# RGB_LED_driver.net
KiCad netlist of a schematic drawn in EAGLE
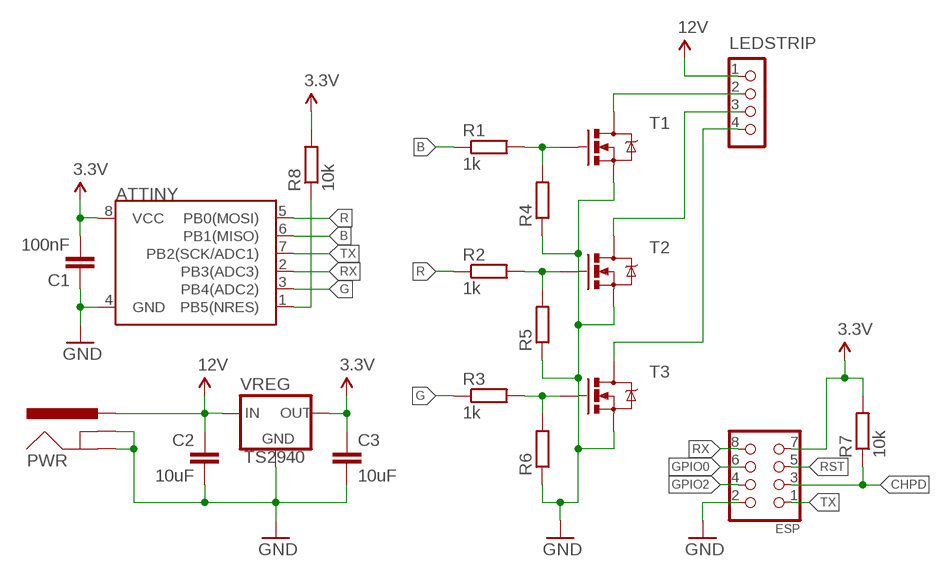
[diagram p0: schematic, sheet 1]

(export (version "E")
  (design (tool "Eeschema 10.0.6"))
  (components
    (comp (ref "ATTINY")
      (value "ATTINY45TINY85-20-SMT")
      (footprint "eagle-import:SO08-EIAJ")
      (libsource (lib "eagle-import") (part "ATTINY45TINY85-20-SMT"))
    )
    (comp (ref "C1")
      (value "100nF")
      (footprint "eagle-import:0805")
      (libsource (lib "eagle-import") (part "CAP0805"))
    )
    (comp (ref "C2")
      (value "10uF")
      (footprint "eagle-import:0805")
      (libsource (lib "eagle-import") (part "CAP0805"))
    )
    (comp (ref "C3")
      (value "10uF")
      (footprint "eagle-import:0805")
      (libsource (lib "eagle-import") (part "CAP0805"))
    )
    (comp (ref "ESP")
      (value "CON_HEADER_2X04-PTH")
      (footprint "eagle-import:M2X4")
      (libsource (lib "eagle-import") (part "CON_HEADER_2X04-PTH"))
    )
    (comp (ref "LEDSTRIP")
      (value "12vBRG")
      (footprint "eagle-import:M1X4")
      (libsource (lib "eagle-import") (part "CON_HEADER_1X04"))
    )
    (comp (ref "PWR")
      (value "POWER_JACKPTH")
      (footprint "eagle-import:POWER_JACK_PTH")
      (libsource (lib "eagle-import") (part "POWER_JACKPTH"))
    )
    (comp (ref "R1")
      (value "1k")
      (footprint "eagle-import:R603")
      (libsource (lib "eagle-import") (part "RESISTOR-0603"))
    )
    (comp (ref "R2")
      (value "1k")
      (footprint "eagle-import:R603")
      (libsource (lib "eagle-import") (part "RESISTOR-0603"))
    )
    (comp (ref "R3")
      (value "1k")
      (footprint "eagle-import:R603")
      (libsource (lib "eagle-import") (part "RESISTOR-0603"))
    )
    (comp (ref "R4")
      (value "RESISTOR-0603")
      (footprint "eagle-import:R603")
      (libsource (lib "eagle-import") (part "RESISTOR-0603"))
    )
    (comp (ref "R5")
      (value "RESISTOR-0603")
      (footprint "eagle-import:R603")
      (libsource (lib "eagle-import") (part "RESISTOR-0603"))
    )
    (comp (ref "R6")
      (value "RESISTOR-0603")
      (footprint "eagle-import:R603")
      (libsource (lib "eagle-import") (part "RESISTOR-0603"))
    )
    (comp (ref "R7")
      (value "10k")
      (footprint "eagle-import:R603")
      (libsource (lib "eagle-import") (part "RESISTOR-0603"))
    )
    (comp (ref "R8")
      (value "10k")
      (footprint "eagle-import:R603")
      (libsource (lib "eagle-import") (part "RESISTOR-0603"))
    )
    (comp (ref "T1")
      (value "MOSFET-NCHANNELFDD8780")
      (footprint "eagle-import:DPAK")
      (libsource (lib "eagle-import") (part "MOSFET-NCHANNELFDD8780"))
    )
    (comp (ref "T2")
      (value "MOSFET-NCHANNELFDD8780")
      (footprint "eagle-import:DPAK")
      (libsource (lib "eagle-import") (part "MOSFET-NCHANNELFDD8780"))
    )
    (comp (ref "T3")
      (value "MOSFET-NCHANNELFDD8780")
      (footprint "eagle-import:DPAK")
      (libsource (lib "eagle-import") (part "MOSFET-NCHANNELFDD8780"))
    )
    (comp (ref "VREG")
      (value "TS2940")
      (footprint "eagle-import:SOT223")
      (libsource (lib "eagle-import") (part "V_REG_MIC2920"))
    )
  )
  (nets
    (net (code "1") (name "3.3V") (class "Default")
      (node (ref "ATTINY") (pin "8") (pinfunction "VCC_8") (pintype "bidirectional"))
      (node (ref "C1") (pin "2") (pinfunction "2_2") (pintype "passive"))
      (node (ref "C3") (pin "1") (pinfunction "1_1") (pintype "passive"))
      (node (ref "ESP") (pin "7") (pinfunction "P$7_7") (pintype "passive"))
      (node (ref "R7") (pin "2") (pinfunction "2_2") (pintype "passive"))
      (node (ref "R8") (pin "2") (pinfunction "2_2") (pintype "passive"))
      (node (ref "VREG") (pin "3") (pinfunction "OUT_3") (pintype "output"))
    )
    (net (code "2") (name "12V") (class "Default")
      (node (ref "C2") (pin "1") (pinfunction "1_1") (pintype "passive"))
      (node (ref "LEDSTRIP") (pin "1") (pinfunction "1_1") (pintype "bidirectional"))
      (node (ref "PWR") (pin "PWR") (pinfunction "PWR_PWR") (pintype "bidirectional"))
      (node (ref "VREG") (pin "1") (pinfunction "IN_1") (pintype "input"))
    )
    (net (code "3") (name "B") (class "Default")
      (node (ref "ATTINY") (pin "6") (pinfunction "PB1(MISO)_6") (pintype "bidirectional"))
      (node (ref "R1") (pin "1") (pinfunction "1_1") (pintype "passive"))
    )
    (net (code "4") (name "CHPD") (class "Default")
      (node (ref "ESP") (pin "3") (pinfunction "P$3_3") (pintype "passive"))
      (node (ref "R7") (pin "1") (pinfunction "1_1") (pintype "passive"))
    )
    (net (code "5") (name "G") (class "Default")
      (node (ref "ATTINY") (pin "3") (pinfunction "PB4(ADC2)_3") (pintype "bidirectional"))
      (node (ref "R3") (pin "1") (pinfunction "1_1") (pintype "passive"))
    )
    (net (code "6") (name "GND") (class "Default")
      (node (ref "ATTINY") (pin "4") (pinfunction "GND_4") (pintype "bidirectional"))
      (node (ref "C1") (pin "1") (pinfunction "1_1") (pintype "passive"))
      (node (ref "C2") (pin "2") (pinfunction "2_2") (pintype "passive"))
      (node (ref "C3") (pin "2") (pinfunction "2_2") (pintype "passive"))
      (node (ref "ESP") (pin "2") (pinfunction "P$2_2") (pintype "passive"))
      (node (ref "PWR") (pin "GND") (pinfunction "GND_GND") (pintype "bidirectional"))
      (node (ref "PWR") (pin "GNDBREAK") (pinfunction "GNDBREAK_GNDBREAK") (pintype "bidirectional"))
      (node (ref "R4") (pin "1") (pinfunction "1_1") (pintype "passive"))
      (node (ref "R5") (pin "1") (pinfunction "1_1") (pintype "passive"))
      (node (ref "R6") (pin "1") (pinfunction "1_1") (pintype "passive"))
      (node (ref "T1") (pin "3") (pinfunction "S_3") (pintype "passive"))
      (node (ref "T2") (pin "3") (pinfunction "S_3") (pintype "passive"))
      (node (ref "T3") (pin "3") (pinfunction "S_3") (pintype "passive"))
      (node (ref "VREG") (pin "2") (pinfunction "GND_2") (pintype "input"))
      (node (ref "VREG") (pin "4") (pinfunction "GND_4") (pintype "input"))
    )
    (net (code "7") (name "GPIO0") (class "Default")
      (node (ref "ESP") (pin "6") (pinfunction "P$6_6") (pintype "passive"))
    )
    (net (code "8") (name "GPIO2") (class "Default")
      (node (ref "ESP") (pin "4") (pinfunction "P$4_4") (pintype "passive"))
    )
    (net (code "9") (name "Net-(ATTINY-PB5(NRES))") (class "Default")
      (node (ref "ATTINY") (pin "1") (pinfunction "PB5(NRES)_1") (pintype "bidirectional"))
      (node (ref "R8") (pin "1") (pinfunction "1_1") (pintype "passive"))
    )
    (net (code "10") (name "Net-(T1-D)") (class "Default")
      (node (ref "LEDSTRIP") (pin "2") (pinfunction "2_2") (pintype "bidirectional"))
      (node (ref "T1") (pin "4") (pinfunction "D_4") (pintype "passive"))
    )
    (net (code "11") (name "Net-(T1-G)") (class "Default")
      (node (ref "R1") (pin "2") (pinfunction "2_2") (pintype "passive"))
      (node (ref "R4") (pin "2") (pinfunction "2_2") (pintype "passive"))
      (node (ref "T1") (pin "1") (pinfunction "G_1") (pintype "passive"))
    )
    (net (code "12") (name "Net-(T2-D)") (class "Default")
      (node (ref "LEDSTRIP") (pin "3") (pinfunction "3_3") (pintype "bidirectional"))
      (node (ref "T2") (pin "4") (pinfunction "D_4") (pintype "passive"))
    )
    (net (code "13") (name "Net-(T2-G)") (class "Default")
      (node (ref "R2") (pin "2") (pinfunction "2_2") (pintype "passive"))
      (node (ref "R5") (pin "2") (pinfunction "2_2") (pintype "passive"))
      (node (ref "T2") (pin "1") (pinfunction "G_1") (pintype "passive"))
    )
    (net (code "14") (name "Net-(T3-D)") (class "Default")
      (node (ref "LEDSTRIP") (pin "4") (pinfunction "4_4") (pintype "bidirectional"))
      (node (ref "T3") (pin "4") (pinfunction "D_4") (pintype "passive"))
    )
    (net (code "15") (name "Net-(T3-G)") (class "Default")
      (node (ref "R3") (pin "2") (pinfunction "2_2") (pintype "passive"))
      (node (ref "R6") (pin "2") (pinfunction "2_2") (pintype "passive"))
      (node (ref "T3") (pin "1") (pinfunction "G_1") (pintype "passive"))
    )
    (net (code "16") (name "R") (class "Default")
      (node (ref "ATTINY") (pin "5") (pinfunction "PB0(MOSI)_5") (pintype "bidirectional"))
      (node (ref "R2") (pin "1") (pinfunction "1_1") (pintype "passive"))
    )
    (net (code "17") (name "RST") (class "Default")
      (node (ref "ESP") (pin "5") (pinfunction "P$5_5") (pintype "passive"))
    )
    (net (code "18") (name "RX") (class "Default")
      (node (ref "ATTINY") (pin "2") (pinfunction "PB3(ADC3)_2") (pintype "bidirectional"))
      (node (ref "ESP") (pin "8") (pinfunction "P$8_8") (pintype "passive"))
    )
    (net (code "19") (name "TX") (class "Default")
      (node (ref "ATTINY") (pin "7") (pinfunction "PB2(SCK/ADC1)_7") (pintype "bidirectional"))
      (node (ref "ESP") (pin "1") (pinfunction "P$1_1") (pintype "passive"))
    )
  )
)
